# rapidshark-main-breakout-top-teensy-mk-1.net
KiCad netlist of a schematic drawn in EAGLE
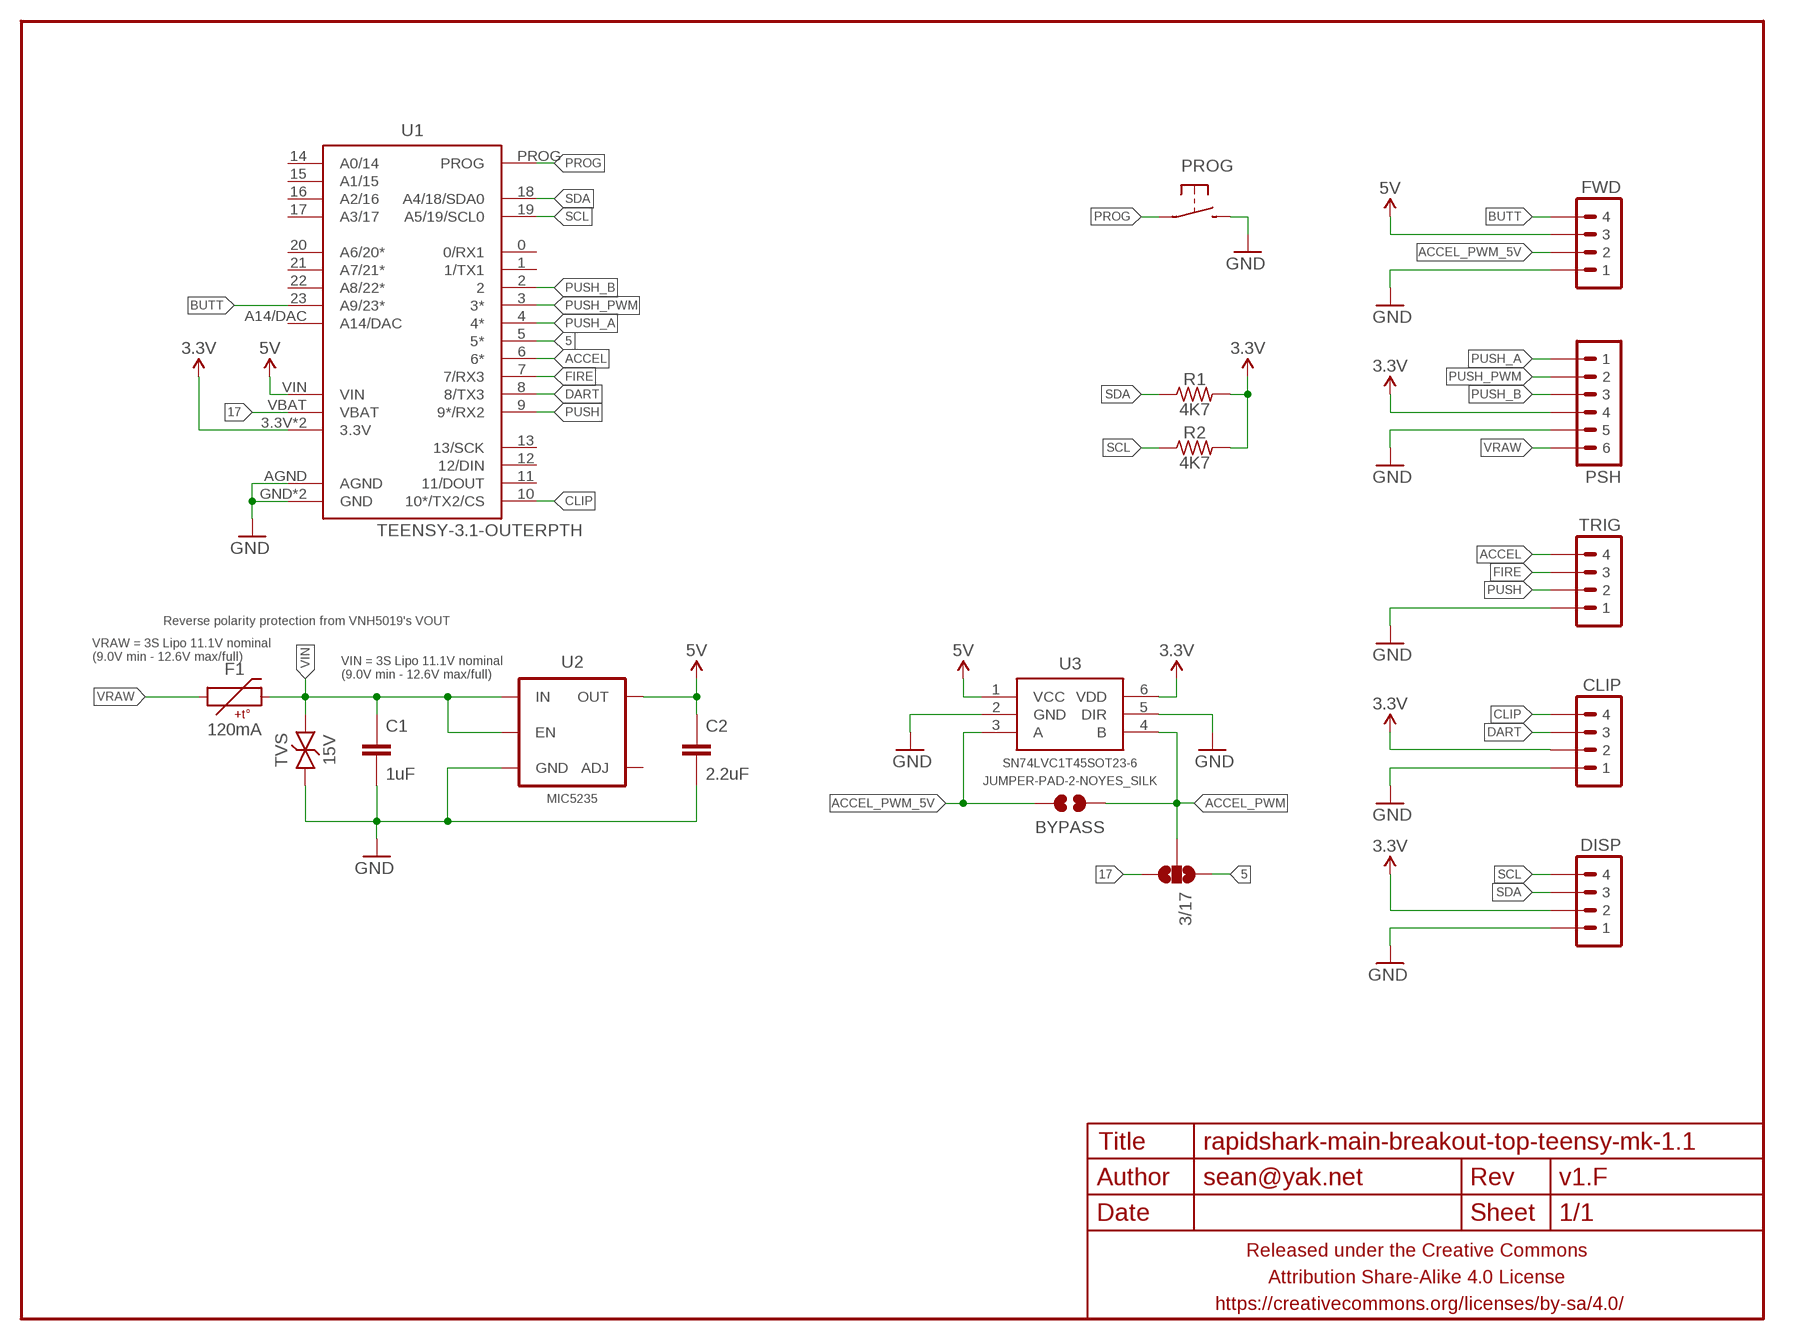
[diagram p0: schematic, sheet 1]

(export (version "E")
  (design (tool "Eeschema 10.0.6"))
  (components
    (comp (ref "3/17")
      (value "JUMPER-PAD-3-NOSMALLER")
      (footprint "eagle-import:PAD-JUMPER-3-NO_YES_SILK_FULL_BOX_SMALLER")
      (libsource (lib "eagle-import") (part "JUMPER-PAD-3-NOSMALLER"))
    )
    (comp (ref "BYPASS")
      (value "JUMPER-PAD-2-NOYES_SILK")
      (footprint "eagle-import:PAD-JUMPER-2-NO_YES_SILK")
      (libsource (lib "eagle-import") (part "JUMPER-PAD-2-NOYES_SILK"))
    )
    (comp (ref "C1")
      (value "1uF")
      (footprint "eagle-import:C0603-TIGHTER")
      (libsource (lib "eagle-import") (part "CAPACITOR-CERAMICC0603-TIGHTER"))
    )
    (comp (ref "C2")
      (value "2.2uF")
      (footprint "eagle-import:C0603-TIGHTER")
      (libsource (lib "eagle-import") (part "CAPACITOR-CERAMICC0603-TIGHTER"))
    )
    (comp (ref "CLIP")
      (value "M04JST-PTH-VERT")
      (footprint "eagle-import:JST-4-PH-VERT-PTH")
      (libsource (lib "eagle-import") (part "M04JST-PTH-VERT"))
    )
    (comp (ref "DISP")
      (value "M04JST-PTH-VERT")
      (footprint "eagle-import:JST-4-PH-VERT-PTH")
      (libsource (lib "eagle-import") (part "M04JST-PTH-VERT"))
    )
    (comp (ref "F1")
      (value "120mA")
      (footprint "eagle-import:PTC-1206")
      (libsource (lib "eagle-import") (part "PTCSMD"))
    )
    (comp (ref "FRAME1")
      (value "FRAME-LETTERNO_PACKAGE")
      (footprint "eagle-import:DUMMY")
      (fields (field (name "DESIGNER") "sean@yak.net") (field (name "VERSION") "v1.F"))
      (libsource (lib "eagle-import") (part "FRAME-LETTERNO_PACKAGE"))
    )
    (comp (ref "FWD")
      (value "M04JST-PTH-VERT")
      (footprint "eagle-import:JST-4-PH-VERT-PTH")
      (libsource (lib "eagle-import") (part "M04JST-PTH-VERT"))
    )
    (comp (ref "PROG")
      (value "SPST-NO-TACTCK-PTS840-GK")
      (footprint "eagle-import:TACTILE-SMD-CK-PTS840-GK")
      (libsource (lib "eagle-import") (part "SPST-NO-TACTCK-PTS840-GK"))
    )
    (comp (ref "PSH")
      (value "M06JST-PH-PTH-VERT")
      (footprint "eagle-import:JST-6-PH-VERT-PTH")
      (libsource (lib "eagle-import") (part "M06JST-PH-PTH-VERT"))
    )
    (comp (ref "R1")
      (value "4K7")
      (footprint "eagle-import:R0603-TIGHTER")
      (libsource (lib "eagle-import") (part "RESISTORR0603-TIGHTER"))
    )
    (comp (ref "R2")
      (value "4K7")
      (footprint "eagle-import:R0603-TIGHTER")
      (libsource (lib "eagle-import") (part "RESISTORR0603-TIGHTER"))
    )
    (comp (ref "TRIG")
      (value "M04JST-PTH-VERT")
      (footprint "eagle-import:JST-4-PH-VERT-PTH")
      (libsource (lib "eagle-import") (part "M04JST-PTH-VERT"))
    )
    (comp (ref "TVS")
      (value "15V")
      (footprint "eagle-import:SMA-DIODE-TVS-BIDIR")
      (libsource (lib "eagle-import") (part "TVSSMA"))
    )
    (comp (ref "U1")
      (value "TEENSY-3.1-OUTERPTH")
      (footprint "eagle-import:TEENSY-3.1_OUTERONLY")
      (libsource (lib "eagle-import") (part "TEENSY-3.1-OUTERPTH"))
    )
    (comp (ref "U2")
      (value "MIC5235")
      (footprint "eagle-import:SOT23-5")
      (libsource (lib "eagle-import") (part "V_REG_MIC5235"))
    )
    (comp (ref "U3")
      (value "SN74LVC1T45SOT23-6")
      (footprint "eagle-import:SOT23-6")
      (libsource (lib "eagle-import") (part "SN74LVC1T45SOT23-6"))
    )
  )
  (nets
    (net (code "1") (name "3.3V") (class "Default")
      (node (ref "CLIP") (pin "2") (pinfunction "2_2") (pintype "passive"))
      (node (ref "DISP") (pin "2") (pinfunction "2_2") (pintype "passive"))
      (node (ref "PSH") (pin "4") (pinfunction "4_4") (pintype "passive"))
      (node (ref "R1") (pin "2") (pinfunction "2_2") (pintype "passive"))
      (node (ref "R2") (pin "2") (pinfunction "2_2") (pintype "passive"))
      (node (ref "U1") (pin "3.3V") (pinfunction "3.3V_3.3V") (pintype "bidirectional"))
      (node (ref "U1") (pin "3V") (pinfunction "3.3V_3V") (pintype "bidirectional"))
      (node (ref "U3") (pin "6") (pinfunction "VDD_6") (pintype "bidirectional"))
    )
    (net (code "2") (name "5") (class "Default")
      (node (ref "3/17") (pin "1") (pinfunction "1_1") (pintype "passive"))
      (node (ref "U1") (pin "5") (pinfunction "5*_5") (pintype "bidirectional"))
    )
    (net (code "3") (name "5V") (class "Default")
      (node (ref "C2") (pin "1") (pinfunction "1_1") (pintype "passive"))
      (node (ref "FWD") (pin "3") (pinfunction "3_3") (pintype "passive"))
      (node (ref "U1") (pin "VIN") (pinfunction "VIN_VIN") (pintype "bidirectional"))
      (node (ref "U2") (pin "5") (pinfunction "OUT_5") (pintype "passive"))
      (node (ref "U3") (pin "1") (pinfunction "VCC_1") (pintype "bidirectional"))
    )
    (net (code "4") (name "17") (class "Default")
      (node (ref "3/17") (pin "3") (pinfunction "3_3") (pintype "passive"))
      (node (ref "U1") (pin "VBAT") (pinfunction "VBAT_VBAT") (pintype "bidirectional"))
    )
    (net (code "5") (name "ACCEL") (class "Default")
      (node (ref "TRIG") (pin "4") (pinfunction "4_4") (pintype "passive"))
      (node (ref "U1") (pin "6") (pinfunction "6*_6") (pintype "bidirectional"))
    )
    (net (code "6") (name "ACCEL_PWM") (class "Default")
      (node (ref "3/17") (pin "2") (pinfunction "2_2") (pintype "passive"))
      (node (ref "BYPASS") (pin "1") (pinfunction "1_1") (pintype "passive"))
      (node (ref "U3") (pin "4") (pinfunction "B_4") (pintype "bidirectional"))
    )
    (net (code "7") (name "ACCEL_PWM_5V") (class "Default")
      (node (ref "BYPASS") (pin "2") (pinfunction "2_2") (pintype "passive"))
      (node (ref "FWD") (pin "2") (pinfunction "2_2") (pintype "passive"))
      (node (ref "U3") (pin "3") (pinfunction "A_3") (pintype "bidirectional"))
    )
    (net (code "8") (name "BUTT") (class "Default")
      (node (ref "FWD") (pin "4") (pinfunction "4_4") (pintype "passive"))
      (node (ref "U1") (pin "23") (pinfunction "A9/23*_23") (pintype "bidirectional"))
    )
    (net (code "9") (name "CLIP") (class "Default")
      (node (ref "CLIP") (pin "4") (pinfunction "4_4") (pintype "passive"))
      (node (ref "U1") (pin "10") (pinfunction "10*/TX2/CS_10") (pintype "bidirectional"))
    )
    (net (code "10") (name "DART") (class "Default")
      (node (ref "CLIP") (pin "3") (pinfunction "3_3") (pintype "passive"))
      (node (ref "U1") (pin "8") (pinfunction "8/TX3_8") (pintype "bidirectional"))
    )
    (net (code "11") (name "FIRE") (class "Default")
      (node (ref "TRIG") (pin "3") (pinfunction "3_3") (pintype "passive"))
      (node (ref "U1") (pin "7") (pinfunction "7/RX3_7") (pintype "bidirectional"))
    )
    (net (code "12") (name "GND") (class "Default")
      (node (ref "C1") (pin "2") (pinfunction "2_2") (pintype "passive"))
      (node (ref "C2") (pin "2") (pinfunction "2_2") (pintype "passive"))
      (node (ref "CLIP") (pin "1") (pinfunction "1_1") (pintype "passive"))
      (node (ref "DISP") (pin "1") (pinfunction "1_1") (pintype "passive"))
      (node (ref "FWD") (pin "1") (pinfunction "1_1") (pintype "passive"))
      (node (ref "PROG") (pin "3") (pinfunction "2_3") (pintype "passive"))
      (node (ref "PROG") (pin "4") (pinfunction "2_4") (pintype "passive"))
      (node (ref "PSH") (pin "5") (pinfunction "5_5") (pintype "passive"))
      (node (ref "TRIG") (pin "1") (pinfunction "1_1") (pintype "passive"))
      (node (ref "TVS") (pin "1") (pinfunction "1_1") (pintype "passive"))
      (node (ref "U1") (pin "AGND") (pinfunction "AGND_AGND") (pintype "bidirectional"))
      (node (ref "U1") (pin "GND") (pinfunction "GND_GND") (pintype "bidirectional"))
      (node (ref "U1") (pin "GND1") (pinfunction "GND_GND1") (pintype "bidirectional"))
      (node (ref "U2") (pin "2") (pinfunction "GND_2") (pintype "input"))
      (node (ref "U3") (pin "2") (pinfunction "GND_2") (pintype "bidirectional"))
      (node (ref "U3") (pin "5") (pinfunction "DIR_5") (pintype "bidirectional"))
    )
    (net (code "13") (name "PROG") (class "Default")
      (node (ref "PROG") (pin "1") (pinfunction "1_1") (pintype "passive"))
      (node (ref "PROG") (pin "2") (pinfunction "1_2") (pintype "passive"))
      (node (ref "U1") (pin "PROG") (pinfunction "PROG_PROG") (pintype "bidirectional"))
    )
    (net (code "14") (name "PUSH") (class "Default")
      (node (ref "TRIG") (pin "2") (pinfunction "2_2") (pintype "passive"))
      (node (ref "U1") (pin "9") (pinfunction "9*/RX2_9") (pintype "bidirectional"))
    )
    (net (code "15") (name "PUSH_A") (class "Default")
      (node (ref "PSH") (pin "1") (pinfunction "1_1") (pintype "passive"))
      (node (ref "U1") (pin "4") (pinfunction "4*_4") (pintype "bidirectional"))
    )
    (net (code "16") (name "PUSH_B") (class "Default")
      (node (ref "PSH") (pin "3") (pinfunction "3_3") (pintype "passive"))
      (node (ref "U1") (pin "2") (pinfunction "2_2") (pintype "bidirectional"))
    )
    (net (code "17") (name "PUSH_PWM") (class "Default")
      (node (ref "PSH") (pin "2") (pinfunction "2_2") (pintype "passive"))
      (node (ref "U1") (pin "3") (pinfunction "3*_3") (pintype "bidirectional"))
    )
    (net (code "18") (name "SCL") (class "Default")
      (node (ref "DISP") (pin "4") (pinfunction "4_4") (pintype "passive"))
      (node (ref "R2") (pin "1") (pinfunction "1_1") (pintype "passive"))
      (node (ref "U1") (pin "19") (pinfunction "A5/19/SCL0_19") (pintype "bidirectional"))
    )
    (net (code "19") (name "SDA") (class "Default")
      (node (ref "DISP") (pin "3") (pinfunction "3_3") (pintype "passive"))
      (node (ref "R1") (pin "1") (pinfunction "1_1") (pintype "passive"))
      (node (ref "U1") (pin "18") (pinfunction "A4/18/SDA0_18") (pintype "bidirectional"))
    )
    (net (code "20") (name "VIN") (class "Default")
      (node (ref "C1") (pin "1") (pinfunction "1_1") (pintype "passive"))
      (node (ref "F1") (pin "2") (pinfunction "2_2") (pintype "passive"))
      (node (ref "TVS") (pin "2") (pinfunction "2_2") (pintype "passive"))
      (node (ref "U2") (pin "1") (pinfunction "IN_1") (pintype "input"))
      (node (ref "U2") (pin "3") (pinfunction "EN_3") (pintype "input"))
    )
    (net (code "21") (name "VRAW") (class "Default")
      (node (ref "F1") (pin "1") (pinfunction "1_1") (pintype "passive"))
      (node (ref "PSH") (pin "6") (pinfunction "6_6") (pintype "passive"))
    )
    (net (code "22") (name "unconnected-(U1-0{slash}RX1-Pad0)") (class "Default")
      (node (ref "U1") (pin "0") (pinfunction "0/RX1_0") (pintype "bidirectional"))
    )
    (net (code "23") (name "unconnected-(U1-1{slash}TX1-Pad1)") (class "Default")
      (node (ref "U1") (pin "1") (pinfunction "1/TX1_1") (pintype "bidirectional"))
    )
    (net (code "24") (name "unconnected-(U1-11{slash}DOUT-Pad11)") (class "Default")
      (node (ref "U1") (pin "11") (pinfunction "11/DOUT_11") (pintype "bidirectional"))
    )
    (net (code "25") (name "unconnected-(U1-12{slash}DIN-Pad12)") (class "Default")
      (node (ref "U1") (pin "12") (pinfunction "12/DIN_12") (pintype "bidirectional"))
    )
    (net (code "26") (name "unconnected-(U1-13{slash}SCK-Pad13)") (class "Default")
      (node (ref "U1") (pin "13") (pinfunction "13/SCK_13") (pintype "bidirectional"))
    )
    (net (code "27") (name "unconnected-(U1-A0{slash}14-Pad14)") (class "Default")
      (node (ref "U1") (pin "14") (pinfunction "A0/14_14") (pintype "bidirectional"))
    )
    (net (code "28") (name "unconnected-(U1-A1{slash}15-Pad15)") (class "Default")
      (node (ref "U1") (pin "15") (pinfunction "A1/15_15") (pintype "bidirectional"))
    )
    (net (code "29") (name "unconnected-(U1-A2{slash}16-Pad16)") (class "Default")
      (node (ref "U1") (pin "16") (pinfunction "A2/16_16") (pintype "bidirectional"))
    )
    (net (code "30") (name "unconnected-(U1-A3{slash}17-Pad17)") (class "Default")
      (node (ref "U1") (pin "17") (pinfunction "A3/17_17") (pintype "bidirectional"))
    )
    (net (code "31") (name "unconnected-(U1-A6{slash}20*-Pad20)") (class "Default")
      (node (ref "U1") (pin "20") (pinfunction "A6/20*_20") (pintype "bidirectional"))
    )
    (net (code "32") (name "unconnected-(U1-A7{slash}21*-Pad21)") (class "Default")
      (node (ref "U1") (pin "21") (pinfunction "A7/21*_21") (pintype "bidirectional"))
    )
    (net (code "33") (name "unconnected-(U1-A8{slash}22*-Pad22)") (class "Default")
      (node (ref "U1") (pin "22") (pinfunction "A8/22*_22") (pintype "bidirectional"))
    )
    (net (code "34") (name "unconnected-(U1-PadA14{slash}DAC)") (class "Default")
      (node (ref "U1") (pin "A14/DAC") (pinfunction "A14/DAC_A14/DAC") (pintype "bidirectional"))
    )
    (net (code "35") (name "unconnected-(U2-ADJ-Pad4)") (class "Default")
      (node (ref "U2") (pin "4") (pinfunction "ADJ_4") (pintype "input"))
    )
  )
)
